# lipol_source.net
KiCad netlist of a schematic drawn in EAGLE
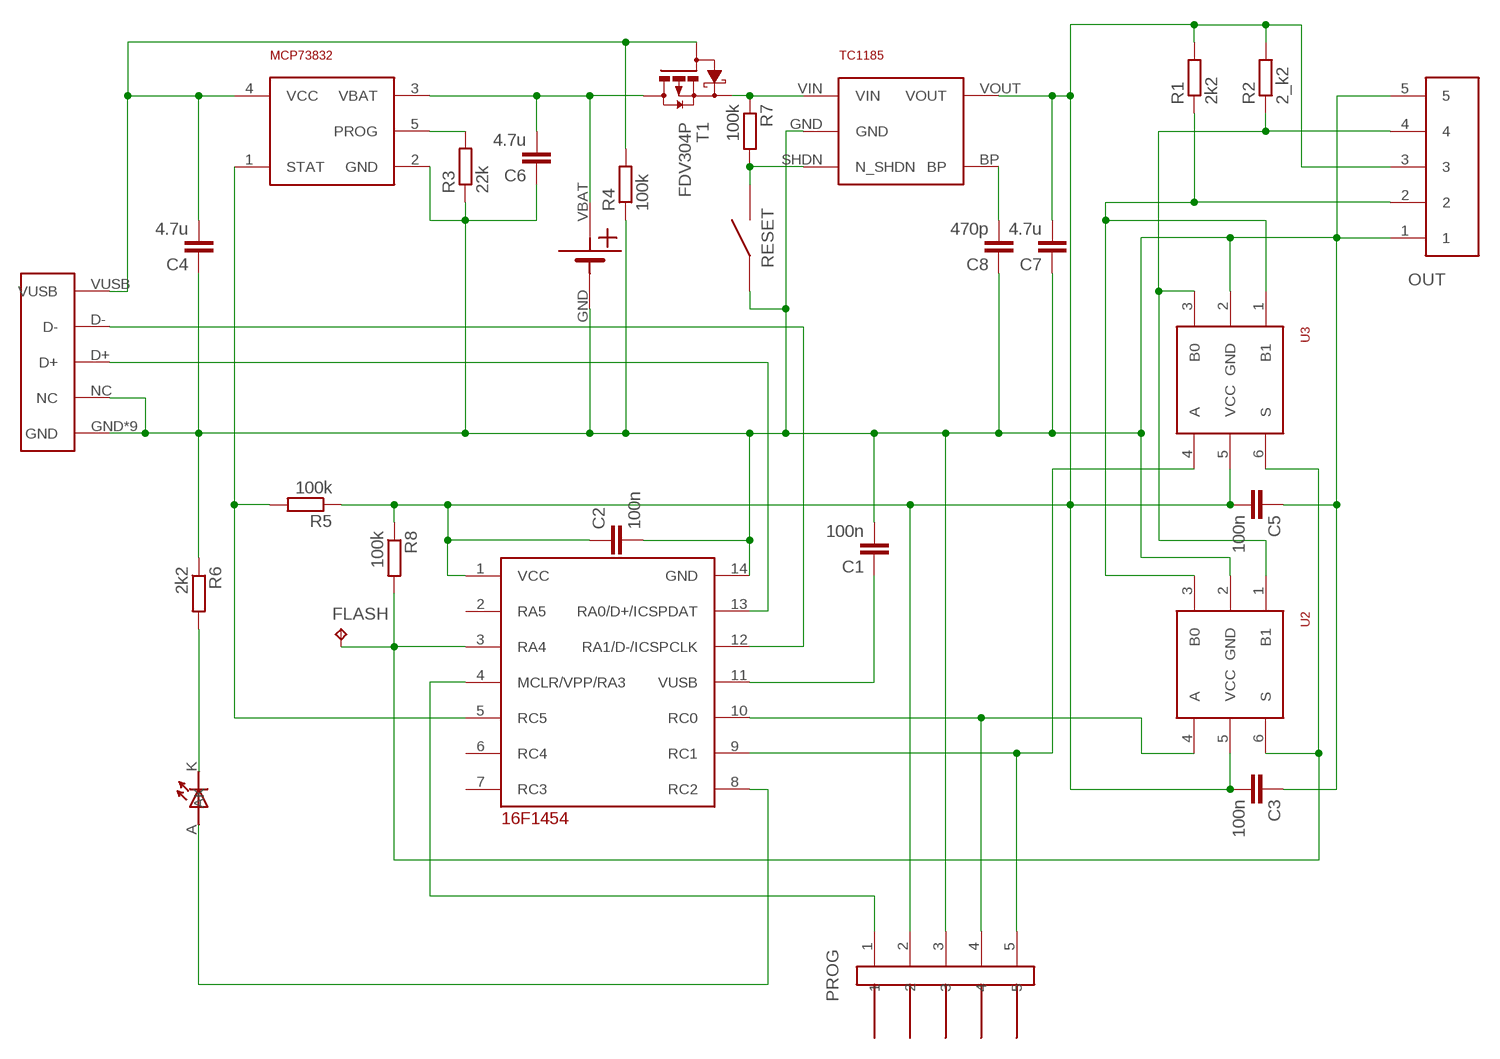
[diagram p0: schematic, sheet 1]

(export (version "E")
  (design (tool "Eeschema 10.0.6"))
  (components
    (comp (ref "C1")
      (value "100n")
      (footprint "eagle-import:C0603K")
      (libsource (lib "eagle-import") (part "C-EUC0603K"))
    )
    (comp (ref "C2")
      (value "100n")
      (footprint "eagle-import:C0603K")
      (libsource (lib "eagle-import") (part "C-EUC0603K"))
    )
    (comp (ref "C3")
      (value "100n")
      (footprint "eagle-import:C0603K")
      (libsource (lib "eagle-import") (part "C-EUC0603K"))
    )
    (comp (ref "C4")
      (value "4.7u")
      (footprint "eagle-import:C0603K")
      (libsource (lib "eagle-import") (part "C-EUC0603K"))
    )
    (comp (ref "C5")
      (value "100n")
      (footprint "eagle-import:C0603K")
      (libsource (lib "eagle-import") (part "C-EUC0603K"))
    )
    (comp (ref "C6")
      (value "4.7u")
      (footprint "eagle-import:C0603K")
      (libsource (lib "eagle-import") (part "C-EUC0603K"))
    )
    (comp (ref "C7")
      (value "4.7u")
      (footprint "eagle-import:C0603K")
      (libsource (lib "eagle-import") (part "C-EUC0603K"))
    )
    (comp (ref "C8")
      (value "470p")
      (footprint "eagle-import:C0603K")
      (libsource (lib "eagle-import") (part "C-EUC0603K"))
    )
    (comp (ref "D1")
      (value "LED1.8")
      (footprint "eagle-import:LED1.8")
      (libsource (lib "eagle-import") (part "LED1.8"))
    )
    (comp (ref "FLASH")
      (value "TPTP10R")
      (footprint "eagle-import:TP10R")
      (libsource (lib "eagle-import") (part "TPTP10R"))
    )
    (comp (ref "MCP73832")
      (value "MCP73831")
      (footprint "eagle-import:SOT23-5")
      (libsource (lib "eagle-import") (part "MCP73831"))
    )
    (comp (ref "OUT")
      (value "JUMPER5F-90")
      (footprint "eagle-import:JUMPER5F-90")
      (libsource (lib "eagle-import") (part "JUMPER5F-90"))
    )
    (comp (ref "PROG")
      (value "JUMPER5M")
      (footprint "eagle-import:JUMPER5M")
      (libsource (lib "eagle-import") (part "JUMPER5M"))
    )
    (comp (ref "R1")
      (value "2k2")
      (footprint "eagle-import:R0603")
      (libsource (lib "eagle-import") (part "R-EU_R0603"))
    )
    (comp (ref "R2")
      (value "2_k2")
      (footprint "eagle-import:R0603")
      (libsource (lib "eagle-import") (part "R-EU_R0603"))
    )
    (comp (ref "R3")
      (value "22k")
      (footprint "eagle-import:R0603")
      (libsource (lib "eagle-import") (part "R-EU_R0603"))
    )
    (comp (ref "R4")
      (value "100k")
      (footprint "eagle-import:R0603")
      (libsource (lib "eagle-import") (part "R-EU_R0603"))
    )
    (comp (ref "R5")
      (value "100k")
      (footprint "eagle-import:R0603")
      (libsource (lib "eagle-import") (part "R-EU_R0603"))
    )
    (comp (ref "R6")
      (value "2k2")
      (footprint "eagle-import:R0603")
      (libsource (lib "eagle-import") (part "R-EU_R0603"))
    )
    (comp (ref "R7")
      (value "100k")
      (footprint "eagle-import:R0603")
      (libsource (lib "eagle-import") (part "R-EU_R0603"))
    )
    (comp (ref "R8")
      (value "100k")
      (footprint "eagle-import:R0603")
      (libsource (lib "eagle-import") (part "R-EU_R0603"))
    )
    (comp (ref "RESET")
      (value "BYTTON-B3U")
      (footprint "eagle-import:BUTTON-B3U")
      (libsource (lib "eagle-import") (part "BYTTON-B3U"))
    )
    (comp (ref "T1")
      (value "FDV304P")
      (footprint "eagle-import:SOT23")
      (libsource (lib "eagle-import") (part "P-MOSFET-FDV304P"))
    )
    (comp (ref "TC1185")
      (value "TC1185")
      (footprint "eagle-import:SOT32-5")
      (libsource (lib "eagle-import") (part "STABILISER_APE8865"))
    )
    (comp (ref "U$3")
      (value "LIPOL_21X17")
      (footprint "eagle-import:LIPOL_21X17")
      (libsource (lib "eagle-import") (part "LIPOL_21X17"))
    )
    (comp (ref "U1")
      (value "16F1454")
      (footprint "eagle-import:TSSOP14")
      (libsource (lib "eagle-import") (part "16F1454"))
    )
    (comp (ref "U2")
      (value "NC7SB3157P6X")
      (footprint "eagle-import:SC70-6L")
      (libsource (lib "eagle-import") (part "NC7SB3157P6X"))
    )
    (comp (ref "U3")
      (value "NC7SB3157P6X")
      (footprint "eagle-import:SC70-6L")
      (libsource (lib "eagle-import") (part "NC7SB3157P6X"))
    )
    (comp (ref "USB")
      (value "USBMICRO")
      (footprint "eagle-import:MICROUSB-MOLEX")
      (libsource (lib "eagle-import") (part "USBMICRO"))
    )
  )
  (nets
    (net (code "1") (name "Net-(C8-Pad2)") (class "Default")
      (node (ref "C8") (pin "2") (pinfunction "2_2") (pintype "passive"))
      (node (ref "TC1185") (pin "BP") (pinfunction "BP_BP") (pintype "bidirectional"))
    )
    (net (code "2") (name "Net-(D1-PadK)") (class "Default")
      (node (ref "D1") (pin "K") (pinfunction "K_K") (pintype "bidirectional"))
      (node (ref "R6") (pin "2") (pinfunction "2_2") (pintype "passive"))
    )
    (net (code "3") (name "Net-(MCP73832-GND)") (class "Default")
      (node (ref "C1") (pin "2") (pinfunction "2_2") (pintype "passive"))
      (node (ref "C2") (pin "2") (pinfunction "2_2") (pintype "passive"))
      (node (ref "C3") (pin "1") (pinfunction "1_1") (pintype "passive"))
      (node (ref "C4") (pin "1") (pinfunction "1_1") (pintype "passive"))
      (node (ref "C5") (pin "1") (pinfunction "1_1") (pintype "passive"))
      (node (ref "C6") (pin "1") (pinfunction "1_1") (pintype "passive"))
      (node (ref "C7") (pin "1") (pinfunction "1_1") (pintype "passive"))
      (node (ref "C8") (pin "1") (pinfunction "1_1") (pintype "passive"))
      (node (ref "MCP73832") (pin "2") (pinfunction "GND_2") (pintype "bidirectional"))
      (node (ref "OUT") (pin "1") (pinfunction "1_1") (pintype "bidirectional"))
      (node (ref "OUT") (pin "5") (pinfunction "5_5") (pintype "bidirectional"))
      (node (ref "PROG") (pin "3") (pinfunction "3_3") (pintype "bidirectional"))
      (node (ref "R3") (pin "1") (pinfunction "1_1") (pintype "passive"))
      (node (ref "R4") (pin "1") (pinfunction "1_1") (pintype "passive"))
      (node (ref "R6") (pin "1") (pinfunction "1_1") (pintype "passive"))
      (node (ref "RESET") (pin "P$1") (pinfunction "P$1_P$1") (pintype "bidirectional"))
      (node (ref "TC1185") (pin "GND") (pinfunction "GND_GND") (pintype "bidirectional"))
      (node (ref "U$3") (pin "GND") (pinfunction "GND_GND") (pintype "power_in"))
      (node (ref "U1") (pin "14") (pinfunction "GND_14") (pintype "power_in"))
      (node (ref "U2") (pin "2") (pinfunction "GND_2") (pintype "power_in"))
      (node (ref "U3") (pin "2") (pinfunction "GND_2") (pintype "power_in"))
      (node (ref "USB") (pin "GND") (pinfunction "GND_GND") (pintype "bidirectional"))
      (node (ref "USB") (pin "GND1") (pinfunction "GND_GND1") (pintype "bidirectional"))
      (node (ref "USB") (pin "GND2") (pinfunction "GND_GND2") (pintype "bidirectional"))
      (node (ref "USB") (pin "GND3") (pinfunction "GND_GND3") (pintype "bidirectional"))
      (node (ref "USB") (pin "GND4") (pinfunction "GND_GND4") (pintype "bidirectional"))
      (node (ref "USB") (pin "NC") (pinfunction "NC_NC") (pintype "bidirectional"))
      (node (ref "USB") (pin "P$1") (pinfunction "GND_P$1") (pintype "bidirectional"))
      (node (ref "USB") (pin "P$2") (pinfunction "GND_P$2") (pintype "bidirectional"))
      (node (ref "USB") (pin "P$3") (pinfunction "GND_P$3") (pintype "bidirectional"))
      (node (ref "USB") (pin "P$6") (pinfunction "GND_P$6") (pintype "bidirectional"))
    )
    (net (code "4") (name "Net-(MCP73832-PROG)") (class "Default")
      (node (ref "MCP73832") (pin "5") (pinfunction "PROG_5") (pintype "bidirectional"))
      (node (ref "R3") (pin "2") (pinfunction "2_2") (pintype "passive"))
    )
    (net (code "5") (name "Net-(MCP73832-STAT)") (class "Default")
      (node (ref "MCP73832") (pin "1") (pinfunction "STAT_1") (pintype "bidirectional"))
      (node (ref "R5") (pin "2") (pinfunction "2_2") (pintype "passive"))
      (node (ref "U1") (pin "5") (pinfunction "RC5_5") (pintype "bidirectional"))
    )
    (net (code "6") (name "Net-(MCP73832-VBAT)") (class "Default")
      (node (ref "C6") (pin "2") (pinfunction "2_2") (pintype "passive"))
      (node (ref "MCP73832") (pin "3") (pinfunction "VBAT_3") (pintype "bidirectional"))
      (node (ref "T1") (pin "D") (pinfunction "D_D") (pintype "passive"))
      (node (ref "U$3") (pin "VBAT") (pinfunction "VBAT_VBAT") (pintype "power_in"))
    )
    (net (code "7") (name "Net-(MCP73832-VCC)") (class "Default")
      (node (ref "C4") (pin "2") (pinfunction "2_2") (pintype "passive"))
      (node (ref "MCP73832") (pin "4") (pinfunction "VCC_4") (pintype "bidirectional"))
      (node (ref "R4") (pin "2") (pinfunction "2_2") (pintype "passive"))
      (node (ref "T1") (pin "G") (pinfunction "G_G") (pintype "passive"))
      (node (ref "USB") (pin "VUSB") (pinfunction "VUSB_VUSB") (pintype "bidirectional"))
    )
    (net (code "8") (name "Net-(R7-Pad1)") (class "Default")
      (node (ref "R7") (pin "1") (pinfunction "1_1") (pintype "passive"))
      (node (ref "T1") (pin "S") (pinfunction "S_S") (pintype "passive"))
      (node (ref "TC1185") (pin "VIN") (pinfunction "VIN_VIN") (pintype "bidirectional"))
    )
    (net (code "9") (name "Net-(TC1185-N_SHDN)") (class "Default")
      (node (ref "R7") (pin "2") (pinfunction "2_2") (pintype "passive"))
      (node (ref "RESET") (pin "P$2") (pinfunction "P$2_P$2") (pintype "bidirectional"))
      (node (ref "TC1185") (pin "SHDN") (pinfunction "N_SHDN_SHDN") (pintype "bidirectional"))
    )
    (net (code "10") (name "Net-(U1-MCLR{slash}VPP{slash}RA3)") (class "Default")
      (node (ref "PROG") (pin "1") (pinfunction "1_1") (pintype "bidirectional"))
      (node (ref "U1") (pin "4") (pinfunction "MCLR/VPP/RA3_4") (pintype "bidirectional"))
    )
    (net (code "11") (name "Net-(U1-RA0{slash}D+{slash}ICSPDAT)") (class "Default")
      (node (ref "U1") (pin "13") (pinfunction "RA0/D+/ICSPDAT_13") (pintype "bidirectional"))
      (node (ref "USB") (pin "D+") (pinfunction "D+_D+") (pintype "bidirectional"))
    )
    (net (code "12") (name "Net-(U1-RA1{slash}D-{slash}ICSPCLK)") (class "Default")
      (node (ref "U1") (pin "12") (pinfunction "RA1/D-/ICSPCLK_12") (pintype "bidirectional"))
      (node (ref "USB") (pin "D-") (pinfunction "D-_D-") (pintype "bidirectional"))
    )
    (net (code "13") (name "Net-(U1-RA4)") (class "Default")
      (node (ref "FLASH") (pin "TP") (pinfunction "TP_TP") (pintype "input"))
      (node (ref "R8") (pin "2") (pinfunction "2_2") (pintype "passive"))
      (node (ref "U1") (pin "3") (pinfunction "RA4_3") (pintype "bidirectional"))
      (node (ref "U2") (pin "6") (pinfunction "S_6") (pintype "bidirectional"))
      (node (ref "U3") (pin "6") (pinfunction "S_6") (pintype "bidirectional"))
    )
    (net (code "14") (name "Net-(U1-RC0)") (class "Default")
      (node (ref "PROG") (pin "4") (pinfunction "4_4") (pintype "bidirectional"))
      (node (ref "U1") (pin "10") (pinfunction "RC0_10") (pintype "bidirectional"))
      (node (ref "U2") (pin "4") (pinfunction "A_4") (pintype "bidirectional"))
    )
    (net (code "15") (name "Net-(U1-RC1)") (class "Default")
      (node (ref "PROG") (pin "5") (pinfunction "5_5") (pintype "bidirectional"))
      (node (ref "U1") (pin "9") (pinfunction "RC1_9") (pintype "bidirectional"))
      (node (ref "U3") (pin "4") (pinfunction "A_4") (pintype "bidirectional"))
    )
    (net (code "16") (name "Net-(U1-RC2)") (class "Default")
      (node (ref "D1") (pin "A") (pinfunction "A_A") (pintype "bidirectional"))
      (node (ref "U1") (pin "8") (pinfunction "RC2_8") (pintype "bidirectional"))
    )
    (net (code "17") (name "Net-(U1-VCC)") (class "Default")
      (node (ref "C2") (pin "1") (pinfunction "1_1") (pintype "passive"))
      (node (ref "C3") (pin "2") (pinfunction "2_2") (pintype "passive"))
      (node (ref "C5") (pin "2") (pinfunction "2_2") (pintype "passive"))
      (node (ref "C7") (pin "2") (pinfunction "2_2") (pintype "passive"))
      (node (ref "OUT") (pin "3") (pinfunction "3_3") (pintype "bidirectional"))
      (node (ref "PROG") (pin "2") (pinfunction "2_2") (pintype "bidirectional"))
      (node (ref "R1") (pin "2") (pinfunction "2_2") (pintype "passive"))
      (node (ref "R2") (pin "2") (pinfunction "2_2") (pintype "passive"))
      (node (ref "R5") (pin "1") (pinfunction "1_1") (pintype "passive"))
      (node (ref "R8") (pin "1") (pinfunction "1_1") (pintype "passive"))
      (node (ref "TC1185") (pin "VOUT") (pinfunction "VOUT_VOUT") (pintype "bidirectional"))
      (node (ref "U1") (pin "1") (pinfunction "VCC_1") (pintype "power_in"))
      (node (ref "U2") (pin "5") (pinfunction "VCC_5") (pintype "power_in"))
      (node (ref "U3") (pin "5") (pinfunction "VCC_5") (pintype "power_in"))
    )
    (net (code "18") (name "Net-(U1-VUSB)") (class "Default")
      (node (ref "C1") (pin "1") (pinfunction "1_1") (pintype "passive"))
      (node (ref "U1") (pin "11") (pinfunction "VUSB_11") (pintype "bidirectional"))
    )
    (net (code "19") (name "Net-(U2-B0)") (class "Default")
      (node (ref "OUT") (pin "2") (pinfunction "2_2") (pintype "bidirectional"))
      (node (ref "R1") (pin "1") (pinfunction "1_1") (pintype "passive"))
      (node (ref "U2") (pin "3") (pinfunction "B0_3") (pintype "bidirectional"))
      (node (ref "U3") (pin "1") (pinfunction "B1_1") (pintype "bidirectional"))
    )
    (net (code "20") (name "Net-(U2-B1)") (class "Default")
      (node (ref "OUT") (pin "4") (pinfunction "4_4") (pintype "bidirectional"))
      (node (ref "R2") (pin "1") (pinfunction "1_1") (pintype "passive"))
      (node (ref "U2") (pin "1") (pinfunction "B1_1") (pintype "bidirectional"))
      (node (ref "U3") (pin "3") (pinfunction "B0_3") (pintype "bidirectional"))
    )
    (net (code "21") (name "unconnected-(U1-RA5-Pad2)") (class "Default")
      (node (ref "U1") (pin "2") (pinfunction "RA5_2") (pintype "bidirectional"))
    )
    (net (code "22") (name "unconnected-(U1-RC3-Pad7)") (class "Default")
      (node (ref "U1") (pin "7") (pinfunction "RC3_7") (pintype "bidirectional"))
    )
    (net (code "23") (name "unconnected-(U1-RC4-Pad6)") (class "Default")
      (node (ref "U1") (pin "6") (pinfunction "RC4_6") (pintype "bidirectional"))
    )
  )
)
